# main_mem.net
KiCad netlist of a schematic drawn in Altium Designer
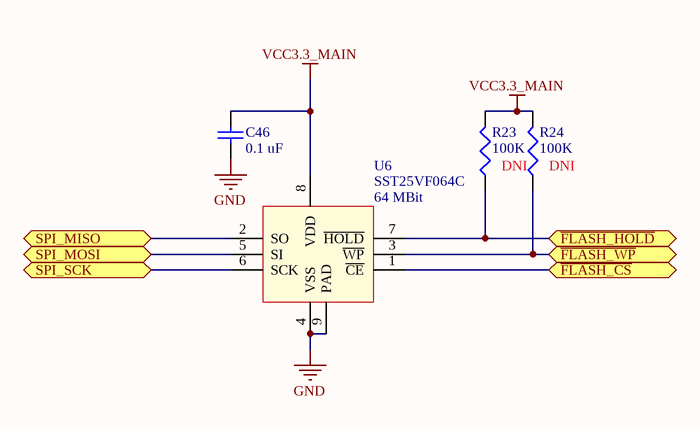
[diagram p0: main_mem.SchDoc]

(export (version "E")
  (design (tool "Eeschema 10.0.6"))
  (components
    (comp (ref "C46")
      (value "0.1 uF")
      (footprint "0402")
      (description "Ceramic capacitor, 0.1u, 0402 package")
      (fields (field (name "TOLERANCE") "10%") (field (name "Comment") "Ceramic capacitor"))
      (libsource (lib "rlc") (part "C_0.1u_0402_ceramic"))
    )
    (comp (ref "R23")
      (value "100K")
      (footprint "0402")
      (description "Chip resistor, 100K, 0402 package")
      (fields (field (name "TOLERANCE") "1%") (field (name "POWER") "1/16 W"))
      (libsource (lib "rlc") (part "R_100K_0402"))
    )
    (comp (ref "R24")
      (value "100K")
      (footprint "0402")
      (description "Chip resistor, 100K, 0402 package")
      (fields (field (name "TOLERANCE") "1%") (field (name "POWER") "1/16 W"))
      (libsource (lib "rlc") (part "R_100K_0402"))
    )
    (comp (ref "U6")
      (value "SST25VF064C")
      (footprint "WSON")
      (description "64 Mbit SPI Serial Dual I/O Flash")
      (fields (field (name "CAPACITY") "64 MBit"))
      (libsource (lib "sdl") (part "SST25VF064C"))
    )
  )
  (nets
    (net (code "1") (name "/SPI_MISO") (class "Default")
      (node (ref "U6") (pin "2") (pinfunction "SO_2") (pintype "passive"))
    )
    (net (code "2") (name "/SPI_MOSI") (class "Default")
      (node (ref "U6") (pin "5") (pinfunction "SI_5") (pintype "passive"))
    )
    (net (code "3") (name "/SPI_SCK") (class "Default")
      (node (ref "U6") (pin "6") (pinfunction "SCK_6") (pintype "passive"))
    )
    (net (code "4") (name "/~{FLASH_CS}") (class "Default")
      (node (ref "U6") (pin "1") (pinfunction "~{CE}_1") (pintype "passive"))
    )
    (net (code "5") (name "/~{FLASH_HOLD}") (class "Default")
      (node (ref "R23") (pin "2") (pintype "passive"))
      (node (ref "U6") (pin "7") (pinfunction "~{HOLD}_7") (pintype "passive"))
    )
    (net (code "6") (name "/~{FLASH_WP}") (class "Default")
      (node (ref "R24") (pin "2") (pintype "passive"))
      (node (ref "U6") (pin "3") (pinfunction "~{WP}_3") (pintype "passive"))
    )
    (net (code "7") (name "GND") (class "Default")
      (node (ref "C46") (pin "2") (pintype "passive"))
      (node (ref "U6") (pin "4") (pinfunction "VSS_4") (pintype "passive"))
      (node (ref "U6") (pin "9") (pinfunction "PAD_9") (pintype "passive"))
    )
    (net (code "8") (name "VCC3.3_MAIN") (class "Default")
      (node (ref "C46") (pin "1") (pintype "passive"))
      (node (ref "R23") (pin "1") (pintype "passive"))
      (node (ref "R24") (pin "1") (pintype "passive"))
      (node (ref "U6") (pin "8") (pinfunction "VDD_8") (pintype "passive"))
    )
  )
)
